# steemdex.net
KiCad netlist of a schematic drawn in EasyEDA
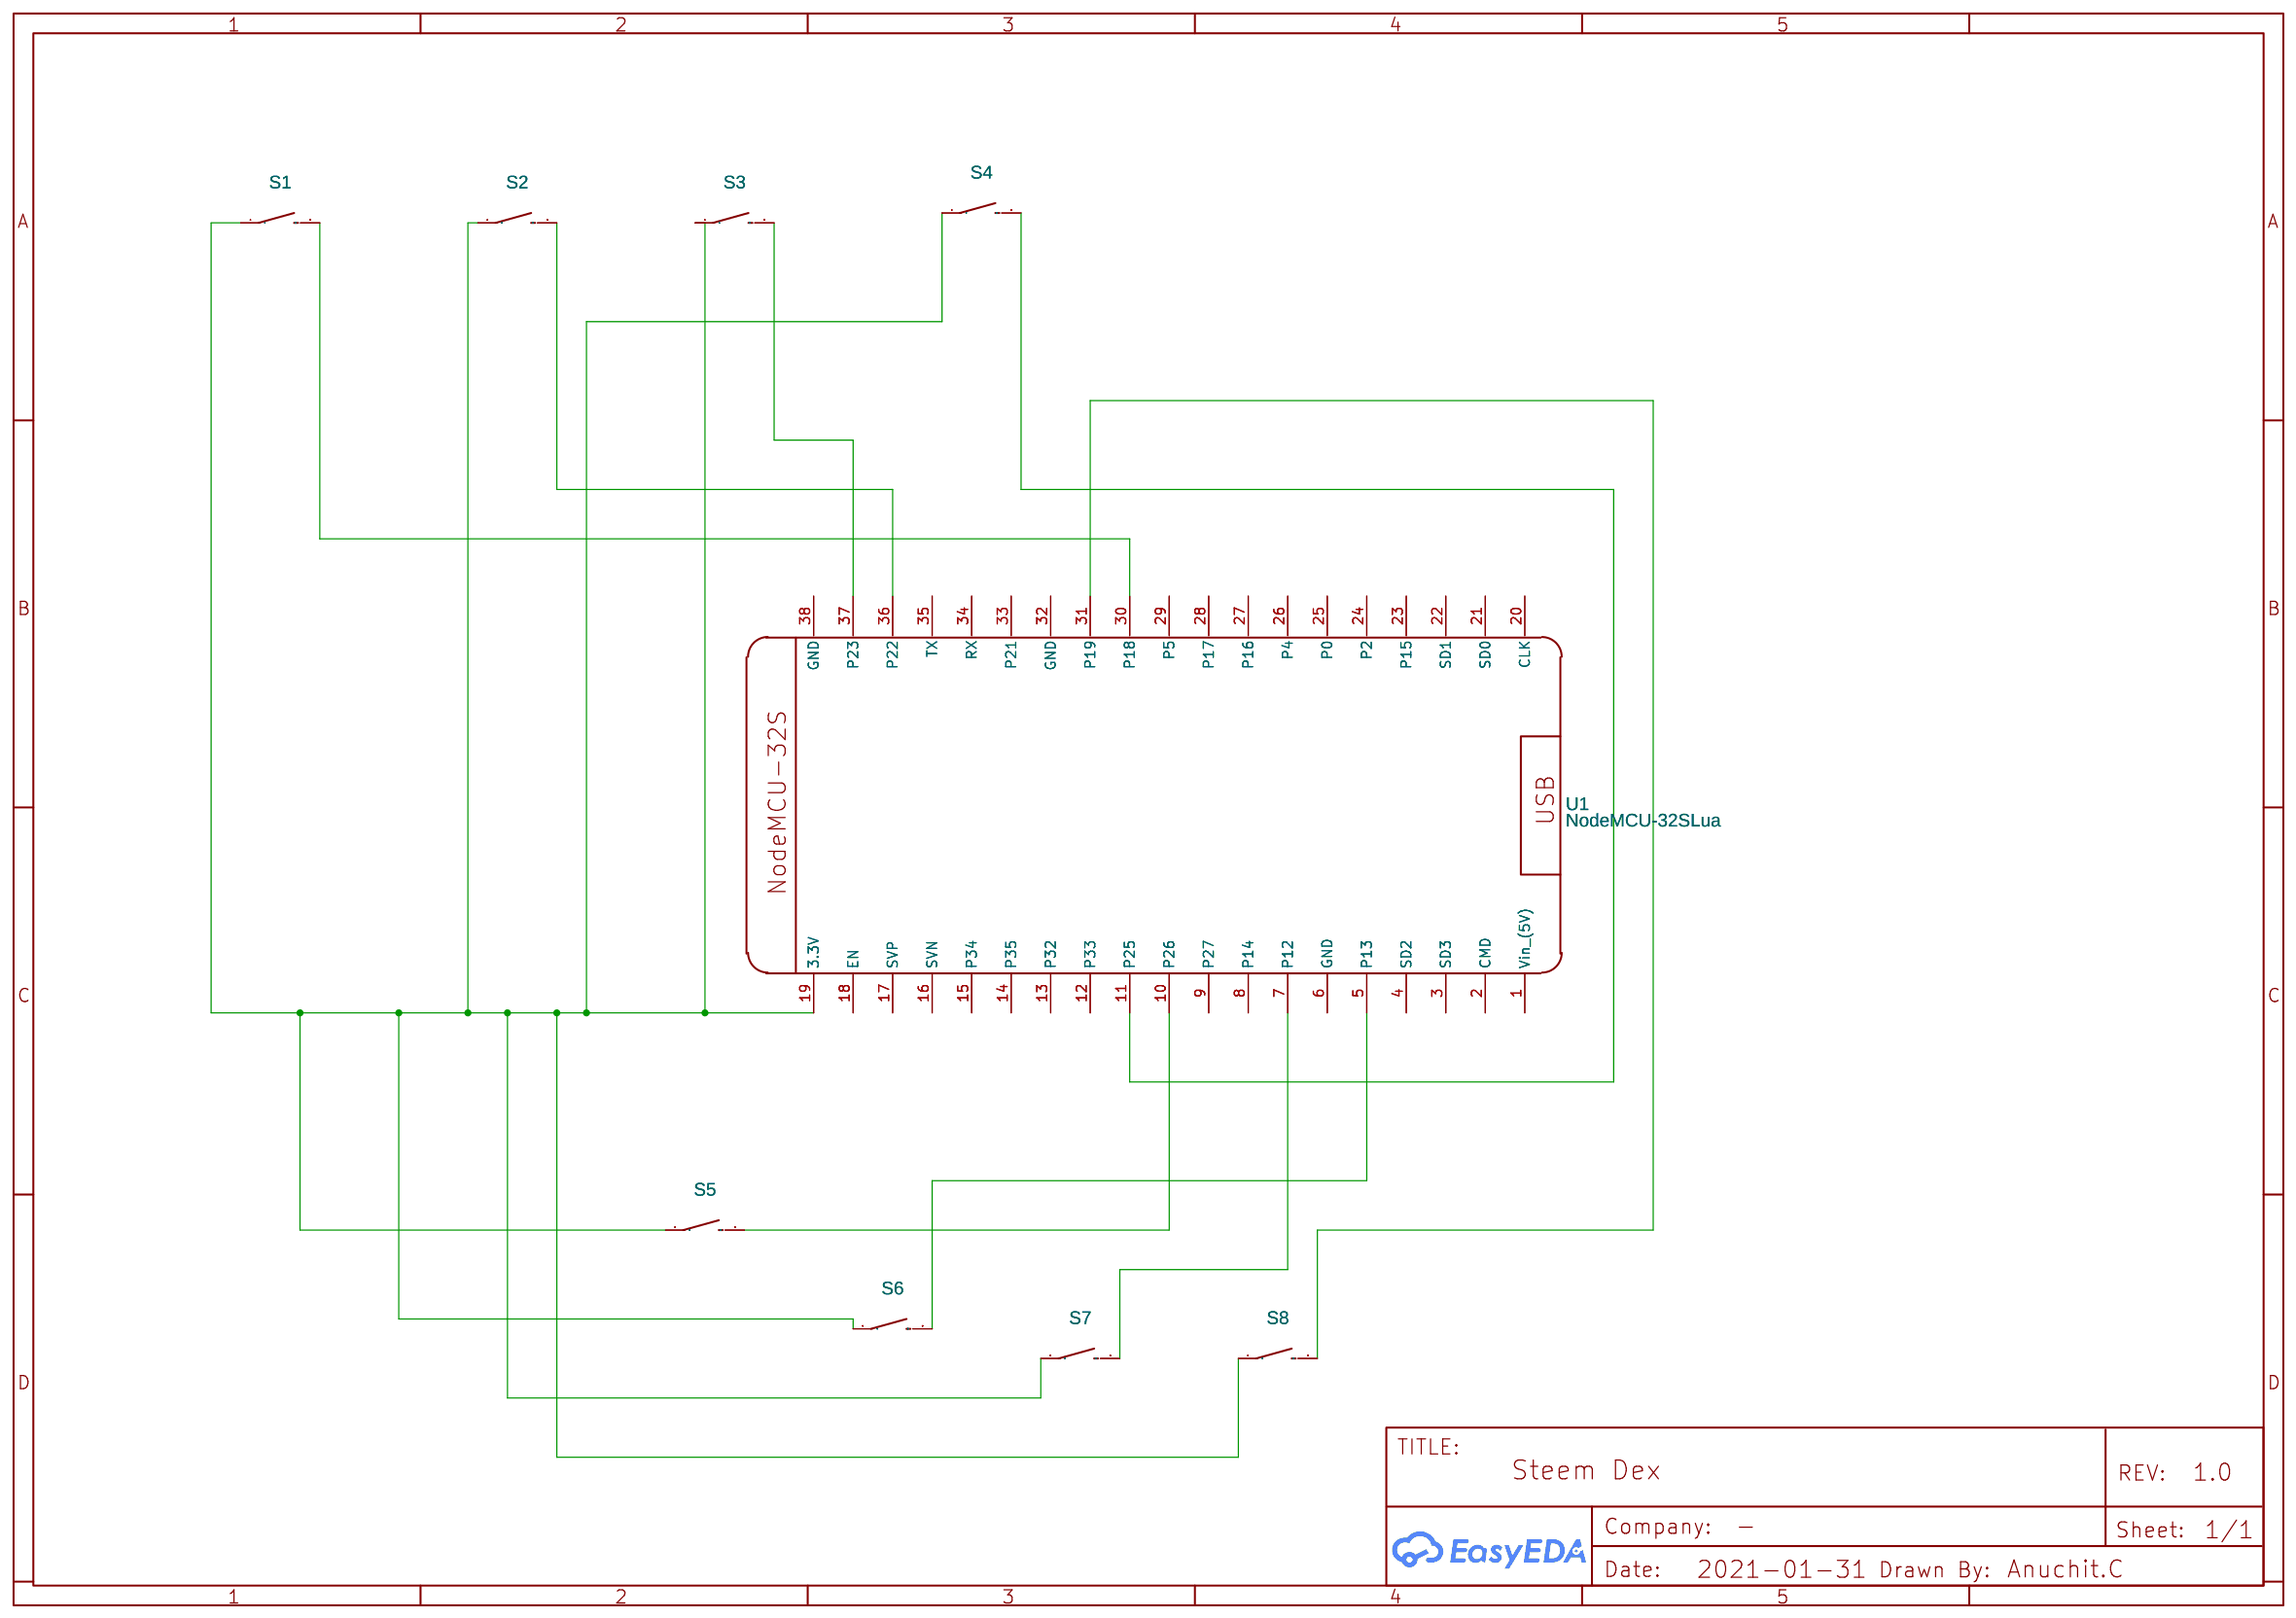
[diagram p0: schematic sheet]

(export (version "E")
  (design (tool "Eeschema 10.0.6"))
  (components
    (comp (ref "S1")
      (value "MOMENTARY-SWITCH-SPST-PTH-12MM")
      (libsource (lib "") (part "MOMENTARY-SWITCH-SPST-PTH-12MM"))
    )
    (comp (ref "S2")
      (value "MOMENTARY-SWITCH-SPST-PTH-12MM")
      (libsource (lib "") (part "MOMENTARY-SWITCH-SPST-PTH-12MM"))
    )
    (comp (ref "S3")
      (value "MOMENTARY-SWITCH-SPST-PTH-12MM")
      (libsource (lib "") (part "MOMENTARY-SWITCH-SPST-PTH-12MM"))
    )
    (comp (ref "S4")
      (value "MOMENTARY-SWITCH-SPST-PTH-12MM")
      (libsource (lib "") (part "MOMENTARY-SWITCH-SPST-PTH-12MM"))
    )
    (comp (ref "S5")
      (value "MOMENTARY-SWITCH-SPST-PTH-12MM")
      (libsource (lib "") (part "MOMENTARY-SWITCH-SPST-PTH-12MM"))
    )
    (comp (ref "S6")
      (value "MOMENTARY-SWITCH-SPST-PTH-12MM")
      (libsource (lib "") (part "MOMENTARY-SWITCH-SPST-PTH-12MM"))
    )
    (comp (ref "S7")
      (value "MOMENTARY-SWITCH-SPST-PTH-12MM")
      (libsource (lib "") (part "MOMENTARY-SWITCH-SPST-PTH-12MM"))
    )
    (comp (ref "S8")
      (value "MOMENTARY-SWITCH-SPST-PTH-12MM")
      (libsource (lib "") (part "MOMENTARY-SWITCH-SPST-PTH-12MM"))
    )
    (comp (ref "U1")
      (value "NodeMCU-32SLua")
      (fields (field (name "BOM_Supplier Part") "C111436"))
      (libsource (lib "") (part "NodeMCU-32SLua"))
    )
  )
  (nets
    (net (code "1") (name "Net-(S1-2)") (class "Default")
      (node (ref "S1") (pin "3") (pinfunction "2_3") (pintype "bidirectional"))
      (node (ref "U1") (pin "30") (pinfunction "P18_30") (pintype "unspecified"))
    )
    (net (code "2") (name "Net-(S2-2)") (class "Default")
      (node (ref "S2") (pin "3") (pinfunction "2_3") (pintype "bidirectional"))
      (node (ref "U1") (pin "36") (pinfunction "P22_36") (pintype "unspecified"))
    )
    (net (code "3") (name "Net-(S3-2)") (class "Default")
      (node (ref "S3") (pin "3") (pinfunction "2_3") (pintype "bidirectional"))
      (node (ref "U1") (pin "37") (pinfunction "P23_37") (pintype "unspecified"))
    )
    (net (code "4") (name "Net-(S4-2)") (class "Default")
      (node (ref "S4") (pin "3") (pinfunction "2_3") (pintype "bidirectional"))
      (node (ref "U1") (pin "11") (pinfunction "P25_11") (pintype "unspecified"))
    )
    (net (code "5") (name "Net-(S5-2)") (class "Default")
      (node (ref "S5") (pin "3") (pinfunction "2_3") (pintype "bidirectional"))
      (node (ref "U1") (pin "10") (pinfunction "P26_10") (pintype "unspecified"))
    )
    (net (code "6") (name "Net-(S6-2)") (class "Default")
      (node (ref "S6") (pin "3") (pinfunction "2_3") (pintype "bidirectional"))
      (node (ref "U1") (pin "5") (pinfunction "P13_5") (pintype "unspecified"))
    )
    (net (code "7") (name "Net-(S7-2)") (class "Default")
      (node (ref "S7") (pin "3") (pinfunction "2_3") (pintype "bidirectional"))
      (node (ref "U1") (pin "7") (pinfunction "P12_7") (pintype "unspecified"))
    )
    (net (code "8") (name "Net-(S8-2)") (class "Default")
      (node (ref "S8") (pin "3") (pinfunction "2_3") (pintype "bidirectional"))
      (node (ref "U1") (pin "31") (pinfunction "P19_31") (pintype "unspecified"))
    )
    (net (code "9") (name "Net-(U1-3.3V)") (class "Default")
      (node (ref "S1") (pin "1") (pinfunction "1_1") (pintype "bidirectional"))
      (node (ref "S2") (pin "1") (pinfunction "1_1") (pintype "bidirectional"))
      (node (ref "S3") (pin "1") (pinfunction "1_1") (pintype "bidirectional"))
      (node (ref "S4") (pin "1") (pinfunction "1_1") (pintype "bidirectional"))
      (node (ref "S5") (pin "1") (pinfunction "1_1") (pintype "bidirectional"))
      (node (ref "S6") (pin "1") (pinfunction "1_1") (pintype "bidirectional"))
      (node (ref "S7") (pin "1") (pinfunction "1_1") (pintype "bidirectional"))
      (node (ref "S8") (pin "1") (pinfunction "1_1") (pintype "bidirectional"))
      (node (ref "U1") (pin "19") (pinfunction "3.3V_19") (pintype "unspecified"))
    )
    (net (code "10") (name "unconnected-(U1-CLK-Pad20)") (class "Default")
      (node (ref "U1") (pin "20") (pinfunction "CLK_20") (pintype "unspecified"))
    )
    (net (code "11") (name "unconnected-(U1-CMD-Pad2)") (class "Default")
      (node (ref "U1") (pin "2") (pinfunction "CMD_2") (pintype "unspecified"))
    )
    (net (code "12") (name "unconnected-(U1-EN-Pad18)") (class "Default")
      (node (ref "U1") (pin "18") (pinfunction "EN_18") (pintype "unspecified"))
    )
    (net (code "13") (name "unconnected-(U1-GND-Pad6)") (class "Default")
      (node (ref "U1") (pin "6") (pinfunction "GND_6") (pintype "unspecified"))
    )
    (net (code "14") (name "unconnected-(U1-GND-Pad32)") (class "Default")
      (node (ref "U1") (pin "32") (pinfunction "GND_32") (pintype "unspecified"))
    )
    (net (code "15") (name "unconnected-(U1-GND-Pad38)") (class "Default")
      (node (ref "U1") (pin "38") (pinfunction "GND_38") (pintype "unspecified"))
    )
    (net (code "16") (name "unconnected-(U1-P0-Pad25)") (class "Default")
      (node (ref "U1") (pin "25") (pinfunction "P0_25") (pintype "unspecified"))
    )
    (net (code "17") (name "unconnected-(U1-P2-Pad24)") (class "Default")
      (node (ref "U1") (pin "24") (pinfunction "P2_24") (pintype "unspecified"))
    )
    (net (code "18") (name "unconnected-(U1-P4-Pad26)") (class "Default")
      (node (ref "U1") (pin "26") (pinfunction "P4_26") (pintype "unspecified"))
    )
    (net (code "19") (name "unconnected-(U1-P5-Pad29)") (class "Default")
      (node (ref "U1") (pin "29") (pinfunction "P5_29") (pintype "unspecified"))
    )
    (net (code "20") (name "unconnected-(U1-P14-Pad8)") (class "Default")
      (node (ref "U1") (pin "8") (pinfunction "P14_8") (pintype "unspecified"))
    )
    (net (code "21") (name "unconnected-(U1-P15-Pad23)") (class "Default")
      (node (ref "U1") (pin "23") (pinfunction "P15_23") (pintype "unspecified"))
    )
    (net (code "22") (name "unconnected-(U1-P16-Pad27)") (class "Default")
      (node (ref "U1") (pin "27") (pinfunction "P16_27") (pintype "unspecified"))
    )
    (net (code "23") (name "unconnected-(U1-P17-Pad28)") (class "Default")
      (node (ref "U1") (pin "28") (pinfunction "P17_28") (pintype "unspecified"))
    )
    (net (code "24") (name "unconnected-(U1-P21-Pad33)") (class "Default")
      (node (ref "U1") (pin "33") (pinfunction "P21_33") (pintype "unspecified"))
    )
    (net (code "25") (name "unconnected-(U1-P27-Pad9)") (class "Default")
      (node (ref "U1") (pin "9") (pinfunction "P27_9") (pintype "unspecified"))
    )
    (net (code "26") (name "unconnected-(U1-P32-Pad13)") (class "Default")
      (node (ref "U1") (pin "13") (pinfunction "P32_13") (pintype "unspecified"))
    )
    (net (code "27") (name "unconnected-(U1-P33-Pad12)") (class "Default")
      (node (ref "U1") (pin "12") (pinfunction "P33_12") (pintype "unspecified"))
    )
    (net (code "28") (name "unconnected-(U1-P34-Pad15)") (class "Default")
      (node (ref "U1") (pin "15") (pinfunction "P34_15") (pintype "unspecified"))
    )
    (net (code "29") (name "unconnected-(U1-P35-Pad14)") (class "Default")
      (node (ref "U1") (pin "14") (pinfunction "P35_14") (pintype "unspecified"))
    )
    (net (code "30") (name "unconnected-(U1-RX-Pad34)") (class "Default")
      (node (ref "U1") (pin "34") (pinfunction "RX_34") (pintype "unspecified"))
    )
    (net (code "31") (name "unconnected-(U1-SD0-Pad21)") (class "Default")
      (node (ref "U1") (pin "21") (pinfunction "SD0_21") (pintype "unspecified"))
    )
    (net (code "32") (name "unconnected-(U1-SD1-Pad22)") (class "Default")
      (node (ref "U1") (pin "22") (pinfunction "SD1_22") (pintype "unspecified"))
    )
    (net (code "33") (name "unconnected-(U1-SD2-Pad4)") (class "Default")
      (node (ref "U1") (pin "4") (pinfunction "SD2_4") (pintype "unspecified"))
    )
    (net (code "34") (name "unconnected-(U1-SD3-Pad3)") (class "Default")
      (node (ref "U1") (pin "3") (pinfunction "SD3_3") (pintype "unspecified"))
    )
    (net (code "35") (name "unconnected-(U1-SVN-Pad16)") (class "Default")
      (node (ref "U1") (pin "16") (pinfunction "SVN_16") (pintype "unspecified"))
    )
    (net (code "36") (name "unconnected-(U1-SVP-Pad17)") (class "Default")
      (node (ref "U1") (pin "17") (pinfunction "SVP_17") (pintype "unspecified"))
    )
    (net (code "37") (name "unconnected-(U1-TX-Pad35)") (class "Default")
      (node (ref "U1") (pin "35") (pinfunction "TX_35") (pintype "unspecified"))
    )
    (net (code "38") (name "unconnected-(U1-Vin_(5V)-Pad1)") (class "Default")
      (node (ref "U1") (pin "1") (pinfunction "Vin_(5V)_1") (pintype "unspecified"))
    )
  )
)
